# body2.net
KiCad netlist of a schematic drawn in Altium Designer
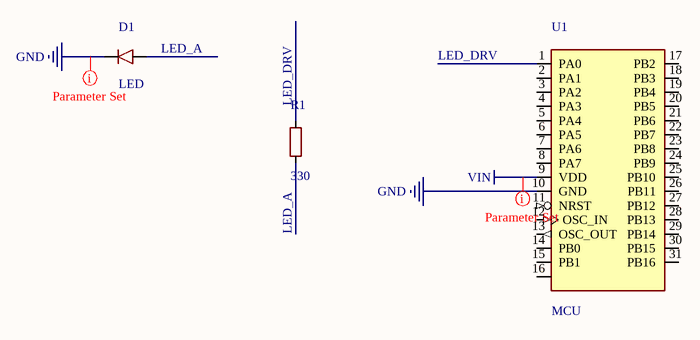
[diagram p0: body2.SchDoc]

(export (version "E")
  (design (tool "Eeschema 10.0.6"))
  (components
    (comp (ref "D1")
      (value "LED")
      (footprint "body2:Mini_LED_THT_3mm")
      (libsource (lib "body2") (part "Mini_LED"))
    )
    (comp (ref "R1") (value "330") (footprint "body2:Mini_R_0603") (libsource (lib "body2") (part "Mini_R")))
    (comp (ref "U1")
      (value "MCU")
      (footprint "body2:Mini_QFP-32_7x7mm_P0.8mm")
      (libsource (lib "body2") (part "Mini_QFP32_IC"))
    )
  )
  (nets
    (net (code "1") (name "/LED_A") (class "Default")
      (node (ref "D1") (pin "2") (pinfunction "A_2") (pintype "passive"))
      (node (ref "R1") (pin "2") (pintype "passive"))
    )
    (net (code "2") (name "/LED_DRV") (class "Default")
      (node (ref "R1") (pin "1") (pintype "passive"))
      (node (ref "U1") (pin "1") (pinfunction "PA0_1") (pintype "bidirectional"))
    )
    (net (code "3") (name "GND") (class "Default")
      (node (ref "D1") (pin "1") (pinfunction "K_1") (pintype "passive"))
      (node (ref "U1") (pin "10") (pinfunction "GND_10") (pintype "power_in"))
    )
    (net (code "4") (name "VIN") (class "Default")
      (node (ref "U1") (pin "9") (pinfunction "VDD_9") (pintype "power_in"))
    )
    (net (code "5") (name "unconnected-(U1-EP-Pad32)") (class "Default")
      (node (ref "U1") (pin "32") (pinfunction "EP_32") (pintype "passive"))
    )
    (net (code "6") (name "unconnected-(U1-NRST-Pad11)") (class "Default")
      (node (ref "U1") (pin "11") (pinfunction "NRST_11") (pintype "input"))
    )
    (net (code "7") (name "unconnected-(U1-OSC_IN-Pad12)") (class "Default")
      (node (ref "U1") (pin "12") (pinfunction "OSC_IN_12") (pintype "input"))
    )
    (net (code "8") (name "unconnected-(U1-OSC_OUT-Pad13)") (class "Default")
      (node (ref "U1") (pin "13") (pinfunction "OSC_OUT_13") (pintype "output"))
    )
    (net (code "9") (name "unconnected-(U1-PA1-Pad2)") (class "Default")
      (node (ref "U1") (pin "2") (pinfunction "PA1_2") (pintype "bidirectional"))
    )
    (net (code "10") (name "unconnected-(U1-PA2-Pad3)") (class "Default")
      (node (ref "U1") (pin "3") (pinfunction "PA2_3") (pintype "bidirectional"))
    )
    (net (code "11") (name "unconnected-(U1-PA3-Pad4)") (class "Default")
      (node (ref "U1") (pin "4") (pinfunction "PA3_4") (pintype "bidirectional"))
    )
    (net (code "12") (name "unconnected-(U1-PA4-Pad5)") (class "Default")
      (node (ref "U1") (pin "5") (pinfunction "PA4_5") (pintype "bidirectional"))
    )
    (net (code "13") (name "unconnected-(U1-PA5-Pad6)") (class "Default")
      (node (ref "U1") (pin "6") (pinfunction "PA5_6") (pintype "bidirectional"))
    )
    (net (code "14") (name "unconnected-(U1-PA6-Pad7)") (class "Default")
      (node (ref "U1") (pin "7") (pinfunction "PA6_7") (pintype "bidirectional"))
    )
    (net (code "15") (name "unconnected-(U1-PA7-Pad8)") (class "Default")
      (node (ref "U1") (pin "8") (pinfunction "PA7_8") (pintype "bidirectional"))
    )
    (net (code "16") (name "unconnected-(U1-PB0-Pad14)") (class "Default")
      (node (ref "U1") (pin "14") (pinfunction "PB0_14") (pintype "bidirectional"))
    )
    (net (code "17") (name "unconnected-(U1-PB1-Pad15)") (class "Default")
      (node (ref "U1") (pin "15") (pinfunction "PB1_15") (pintype "tri_state"))
    )
    (net (code "18") (name "unconnected-(U1-PB2-Pad17)") (class "Default")
      (node (ref "U1") (pin "17") (pinfunction "PB2_17") (pintype "bidirectional"))
    )
    (net (code "19") (name "unconnected-(U1-PB3-Pad18)") (class "Default")
      (node (ref "U1") (pin "18") (pinfunction "PB3_18") (pintype "bidirectional"))
    )
    (net (code "20") (name "unconnected-(U1-PB4-Pad19)") (class "Default")
      (node (ref "U1") (pin "19") (pinfunction "PB4_19") (pintype "bidirectional"))
    )
    (net (code "21") (name "unconnected-(U1-PB5-Pad20)") (class "Default")
      (node (ref "U1") (pin "20") (pinfunction "PB5_20") (pintype "bidirectional"))
    )
    (net (code "22") (name "unconnected-(U1-PB6-Pad21)") (class "Default")
      (node (ref "U1") (pin "21") (pinfunction "PB6_21") (pintype "bidirectional"))
    )
    (net (code "23") (name "unconnected-(U1-PB7-Pad22)") (class "Default")
      (node (ref "U1") (pin "22") (pinfunction "PB7_22") (pintype "bidirectional"))
    )
    (net (code "24") (name "unconnected-(U1-PB8-Pad23)") (class "Default")
      (node (ref "U1") (pin "23") (pinfunction "PB8_23") (pintype "bidirectional"))
    )
    (net (code "25") (name "unconnected-(U1-PB9-Pad24)") (class "Default")
      (node (ref "U1") (pin "24") (pinfunction "PB9_24") (pintype "bidirectional"))
    )
    (net (code "26") (name "unconnected-(U1-PB10-Pad25)") (class "Default")
      (node (ref "U1") (pin "25") (pinfunction "PB10_25") (pintype "bidirectional"))
    )
    (net (code "27") (name "unconnected-(U1-PB11-Pad26)") (class "Default")
      (node (ref "U1") (pin "26") (pinfunction "PB11_26") (pintype "bidirectional"))
    )
    (net (code "28") (name "unconnected-(U1-PB12-Pad27)") (class "Default")
      (node (ref "U1") (pin "27") (pinfunction "PB12_27") (pintype "bidirectional"))
    )
    (net (code "29") (name "unconnected-(U1-PB13-Pad28)") (class "Default")
      (node (ref "U1") (pin "28") (pinfunction "PB13_28") (pintype "bidirectional"))
    )
    (net (code "30") (name "unconnected-(U1-PB14-Pad29)") (class "Default")
      (node (ref "U1") (pin "29") (pinfunction "PB14_29") (pintype "bidirectional"))
    )
    (net (code "31") (name "unconnected-(U1-PB15-Pad30)") (class "Default")
      (node (ref "U1") (pin "30") (pinfunction "PB15_30") (pintype "bidirectional"))
    )
    (net (code "32") (name "unconnected-(U1-PB16-Pad31)") (class "Default")
      (node (ref "U1") (pin "31") (pinfunction "PB16_31") (pintype "bidirectional"))
    )
    (net (code "33") (name "unconnected-(U1-Pad16)") (class "Default")
      (node (ref "U1") (pin "16") (pintype "passive"))
    )
  )
)
